# Adafruit_min8x8_backpack.net
KiCad netlist of a schematic drawn in EAGLE
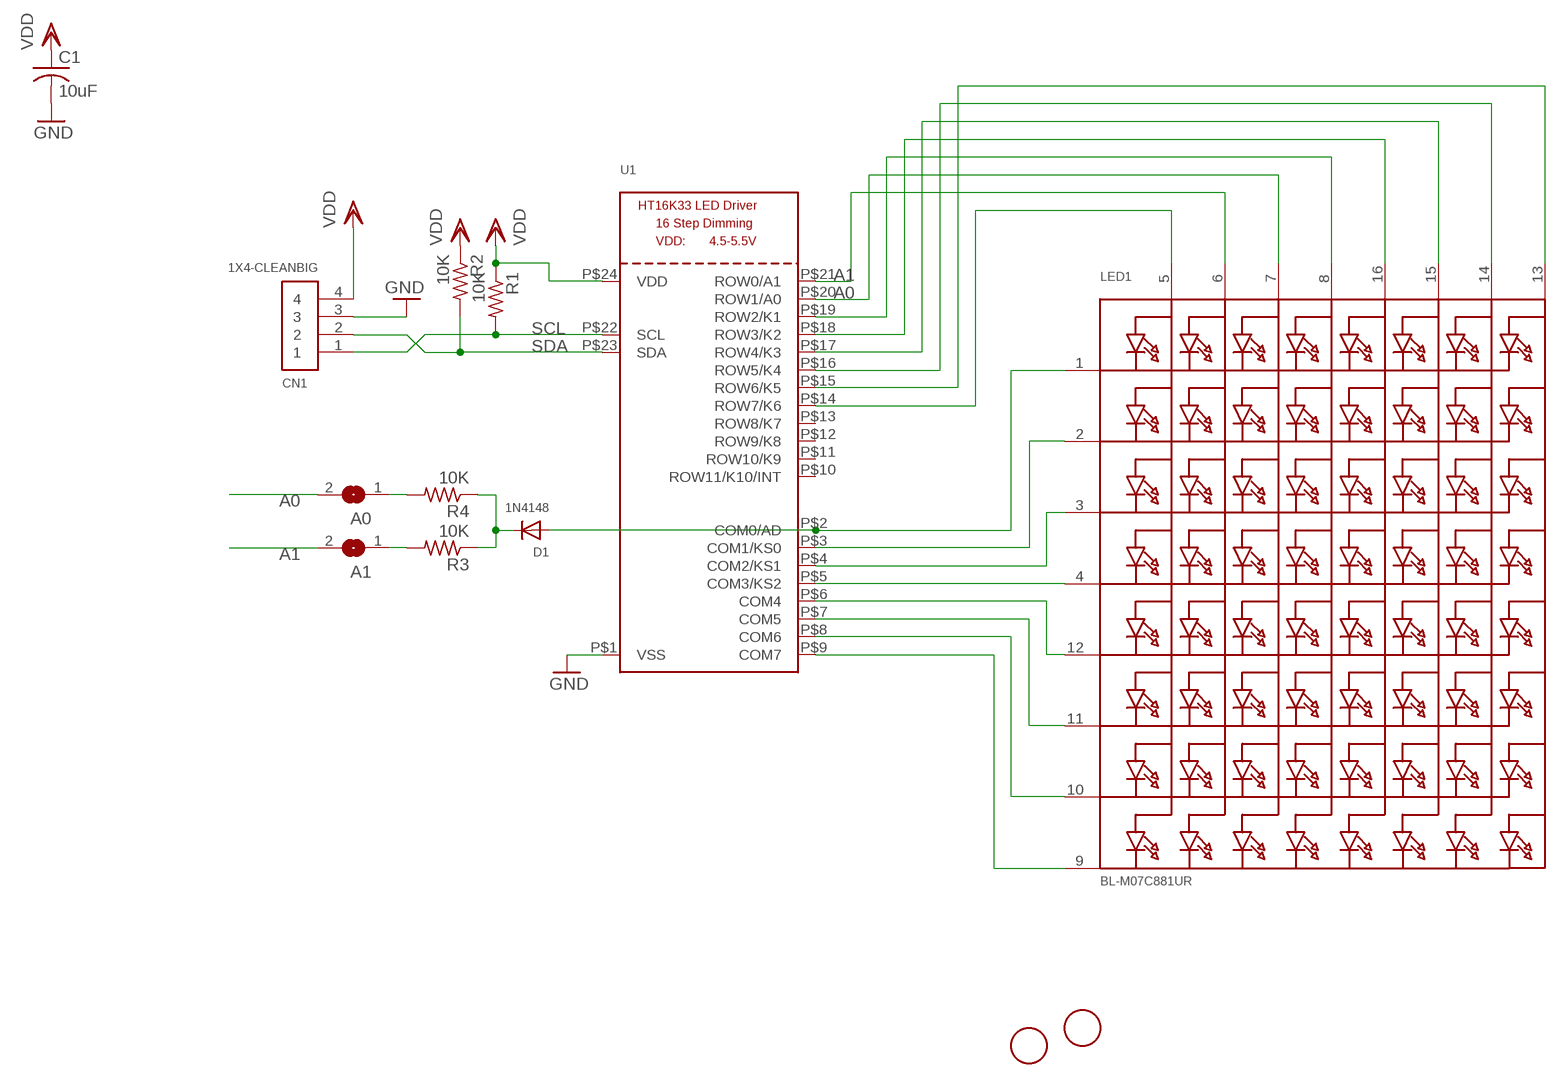
[diagram p0: schematic, sheet 1]

(export (version "E")
  (design (tool "Eeschema 10.0.6"))
  (components
    (comp (ref "A0")
      (value "SOLDERJUMPERREFLOW_NOPASTE")
      (footprint "eagle-import:SOLDERJUMPER_REFLOW_NOPASTE")
      (libsource (lib "eagle-import") (part "SOLDERJUMPERREFLOW_NOPASTE"))
    )
    (comp (ref "A1")
      (value "SOLDERJUMPERREFLOW_NOPASTE")
      (footprint "eagle-import:SOLDERJUMPER_REFLOW_NOPASTE")
      (libsource (lib "eagle-import") (part "SOLDERJUMPERREFLOW_NOPASTE"))
    )
    (comp (ref "C1")
      (value "10uF")
      (footprint "eagle-import:C0805")
      (libsource (lib "eagle-import") (part "C-USC0805"))
    )
    (comp (ref "CN1")
      (value "1X4-CLEANBIG")
      (footprint "eagle-import:1X04-CLEANBIG")
      (libsource (lib "eagle-import") (part "1X4-CLEANBIG"))
    )
    (comp (ref "D1")
      (value "1N4148")
      (footprint "eagle-import:SOD-323F")
      (libsource (lib "eagle-import") (part "DIODESOD-323F"))
    )
    (comp (ref "LED1")
      (value "BL-M07C881UR")
      (footprint "eagle-import:SEGMENT_BL-M07C881UR")
      (libsource (lib "eagle-import") (part "DISP_SEGMENT_8X8_ROWCATHODE"))
    )
    (comp (ref "R1")
      (value "10K")
      (footprint "eagle-import:R0805")
      (libsource (lib "eagle-import") (part "R-US_R0805"))
    )
    (comp (ref "R2")
      (value "10K")
      (footprint "eagle-import:R0805")
      (libsource (lib "eagle-import") (part "R-US_R0805"))
    )
    (comp (ref "R3")
      (value "10K")
      (footprint "eagle-import:R0805")
      (libsource (lib "eagle-import") (part "R-US_R0805"))
    )
    (comp (ref "R4")
      (value "10K")
      (footprint "eagle-import:R0805")
      (libsource (lib "eagle-import") (part "R-US_R0805"))
    )
    (comp (ref "U$1")
      (value "FIDUCIAL")
      (footprint "eagle-import:FIDUCIAL_1MM")
      (libsource (lib "eagle-import") (part "FIDUCIAL"))
    )
    (comp (ref "U$2")
      (value "FIDUCIAL")
      (footprint "eagle-import:FIDUCIAL_1MM")
      (libsource (lib "eagle-import") (part "FIDUCIAL"))
    )
    (comp (ref "U1")
      (value "HT16K33_SOP24")
      (footprint "eagle-import:SOP24_300MIL")
      (libsource (lib "eagle-import") (part "HT16K33_SOP24"))
    )
  )
  (nets
    (net (code "1") (name "/A0") (class "Default")
      (node (ref "A0") (pin "2") (pinfunction "2_2") (pintype "passive"))
      (node (ref "LED1") (pin "7") (pinfunction "A3_7") (pintype "bidirectional"))
      (node (ref "U1") (pin "P$20") (pinfunction "ROW1/A0_P$20") (pintype "bidirectional"))
    )
    (net (code "2") (name "/A1") (class "Default")
      (node (ref "A1") (pin "2") (pinfunction "2_2") (pintype "passive"))
      (node (ref "LED1") (pin "6") (pinfunction "A2_6") (pintype "bidirectional"))
      (node (ref "U1") (pin "P$21") (pinfunction "ROW0/A1_P$21") (pintype "bidirectional"))
    )
    (net (code "3") (name "/SCL") (class "Default")
      (node (ref "CN1") (pin "1") (pinfunction "1_1") (pintype "bidirectional"))
      (node (ref "R1") (pin "2") (pinfunction "2_2") (pintype "passive"))
      (node (ref "U1") (pin "P$22") (pinfunction "SCL_P$22") (pintype "bidirectional"))
    )
    (net (code "4") (name "/SDA") (class "Default")
      (node (ref "CN1") (pin "2") (pinfunction "2_2") (pintype "bidirectional"))
      (node (ref "R2") (pin "2") (pinfunction "2_2") (pintype "passive"))
      (node (ref "U1") (pin "P$23") (pinfunction "SDA_P$23") (pintype "bidirectional"))
    )
    (net (code "5") (name "GND") (class "Default")
      (node (ref "C1") (pin "2") (pinfunction "2_2") (pintype "passive"))
      (node (ref "CN1") (pin "3") (pinfunction "3_3") (pintype "bidirectional"))
      (node (ref "U1") (pin "P$1") (pinfunction "VSS_P$1") (pintype "bidirectional"))
    )
    (net (code "6") (name "Net-(A0-Pad1)") (class "Default")
      (node (ref "A0") (pin "1") (pinfunction "1_1") (pintype "passive"))
      (node (ref "R4") (pin "2") (pinfunction "2_2") (pintype "passive"))
    )
    (net (code "7") (name "Net-(A1-Pad1)") (class "Default")
      (node (ref "A1") (pin "1") (pinfunction "1_1") (pintype "passive"))
      (node (ref "R3") (pin "2") (pinfunction "2_2") (pintype "passive"))
    )
    (net (code "8") (name "Net-(D1-PadC)") (class "Default")
      (node (ref "D1") (pin "C") (pinfunction "C_C") (pintype "passive"))
      (node (ref "R3") (pin "1") (pinfunction "1_1") (pintype "passive"))
      (node (ref "R4") (pin "1") (pinfunction "1_1") (pintype "passive"))
    )
    (net (code "9") (name "Net-(LED1-A1)") (class "Default")
      (node (ref "LED1") (pin "5") (pinfunction "A1_5") (pintype "bidirectional"))
      (node (ref "U1") (pin "P$14") (pinfunction "ROW7/K6_P$14") (pintype "bidirectional"))
    )
    (net (code "10") (name "Net-(LED1-A4)") (class "Default")
      (node (ref "LED1") (pin "8") (pinfunction "A4_8") (pintype "bidirectional"))
      (node (ref "U1") (pin "P$19") (pinfunction "ROW2/K1_P$19") (pintype "bidirectional"))
    )
    (net (code "11") (name "Net-(LED1-A5)") (class "Default")
      (node (ref "LED1") (pin "16") (pinfunction "A5_16") (pintype "bidirectional"))
      (node (ref "U1") (pin "P$18") (pinfunction "ROW3/K2_P$18") (pintype "bidirectional"))
    )
    (net (code "12") (name "Net-(LED1-A6)") (class "Default")
      (node (ref "LED1") (pin "15") (pinfunction "A6_15") (pintype "bidirectional"))
      (node (ref "U1") (pin "P$17") (pinfunction "ROW4/K3_P$17") (pintype "bidirectional"))
    )
    (net (code "13") (name "Net-(LED1-A7)") (class "Default")
      (node (ref "LED1") (pin "14") (pinfunction "A7_14") (pintype "bidirectional"))
      (node (ref "U1") (pin "P$16") (pinfunction "ROW5/K4_P$16") (pintype "bidirectional"))
    )
    (net (code "14") (name "Net-(LED1-A8)") (class "Default")
      (node (ref "LED1") (pin "13") (pinfunction "A8_13") (pintype "bidirectional"))
      (node (ref "U1") (pin "P$15") (pinfunction "ROW6/K5_P$15") (pintype "bidirectional"))
    )
    (net (code "15") (name "Net-(LED1-K1)") (class "Default")
      (node (ref "D1") (pin "A") (pinfunction "A_A") (pintype "passive"))
      (node (ref "LED1") (pin "1") (pinfunction "K1_1") (pintype "bidirectional"))
      (node (ref "U1") (pin "P$2") (pinfunction "COM0/AD_P$2") (pintype "bidirectional"))
    )
    (net (code "16") (name "Net-(LED1-K2)") (class "Default")
      (node (ref "LED1") (pin "2") (pinfunction "K2_2") (pintype "bidirectional"))
      (node (ref "U1") (pin "P$3") (pinfunction "COM1/KS0_P$3") (pintype "bidirectional"))
    )
    (net (code "17") (name "Net-(LED1-K3)") (class "Default")
      (node (ref "LED1") (pin "3") (pinfunction "K3_3") (pintype "bidirectional"))
      (node (ref "U1") (pin "P$4") (pinfunction "COM2/KS1_P$4") (pintype "bidirectional"))
    )
    (net (code "18") (name "Net-(LED1-K4)") (class "Default")
      (node (ref "LED1") (pin "4") (pinfunction "K4_4") (pintype "bidirectional"))
      (node (ref "U1") (pin "P$5") (pinfunction "COM3/KS2_P$5") (pintype "bidirectional"))
    )
    (net (code "19") (name "Net-(LED1-K5)") (class "Default")
      (node (ref "LED1") (pin "12") (pinfunction "K5_12") (pintype "bidirectional"))
      (node (ref "U1") (pin "P$6") (pinfunction "COM4_P$6") (pintype "bidirectional"))
    )
    (net (code "20") (name "Net-(LED1-K6)") (class "Default")
      (node (ref "LED1") (pin "11") (pinfunction "K6_11") (pintype "bidirectional"))
      (node (ref "U1") (pin "P$7") (pinfunction "COM5_P$7") (pintype "bidirectional"))
    )
    (net (code "21") (name "Net-(LED1-K7)") (class "Default")
      (node (ref "LED1") (pin "10") (pinfunction "K7_10") (pintype "bidirectional"))
      (node (ref "U1") (pin "P$8") (pinfunction "COM6_P$8") (pintype "bidirectional"))
    )
    (net (code "22") (name "Net-(LED1-K8)") (class "Default")
      (node (ref "LED1") (pin "9") (pinfunction "K8_9") (pintype "bidirectional"))
      (node (ref "U1") (pin "P$9") (pinfunction "COM7_P$9") (pintype "bidirectional"))
    )
    (net (code "23") (name "VDD") (class "Default")
      (node (ref "C1") (pin "1") (pinfunction "1_1") (pintype "passive"))
      (node (ref "CN1") (pin "4") (pinfunction "4_4") (pintype "bidirectional"))
      (node (ref "R1") (pin "1") (pinfunction "1_1") (pintype "passive"))
      (node (ref "R2") (pin "1") (pinfunction "1_1") (pintype "passive"))
      (node (ref "U1") (pin "P$24") (pinfunction "VDD_P$24") (pintype "bidirectional"))
    )
    (net (code "24") (name "unconnected-(U1-ROW8{slash}K7-PadP$13)") (class "Default")
      (node (ref "U1") (pin "P$13") (pinfunction "ROW8/K7_P$13") (pintype "bidirectional"))
    )
    (net (code "25") (name "unconnected-(U1-ROW9{slash}K8-PadP$12)") (class "Default")
      (node (ref "U1") (pin "P$12") (pinfunction "ROW9/K8_P$12") (pintype "bidirectional"))
    )
    (net (code "26") (name "unconnected-(U1-ROW10{slash}K9-PadP$11)") (class "Default")
      (node (ref "U1") (pin "P$11") (pinfunction "ROW10/K9_P$11") (pintype "bidirectional"))
    )
    (net (code "27") (name "unconnected-(U1-ROW11{slash}K10{slash}INT-PadP$10)") (class "Default")
      (node (ref "U1") (pin "P$10") (pinfunction "ROW11/K10/INT_P$10") (pintype "bidirectional"))
    )
  )
)
